# S-COMERCIALES.net
KiCad netlist of a schematic drawn in Altium Designer
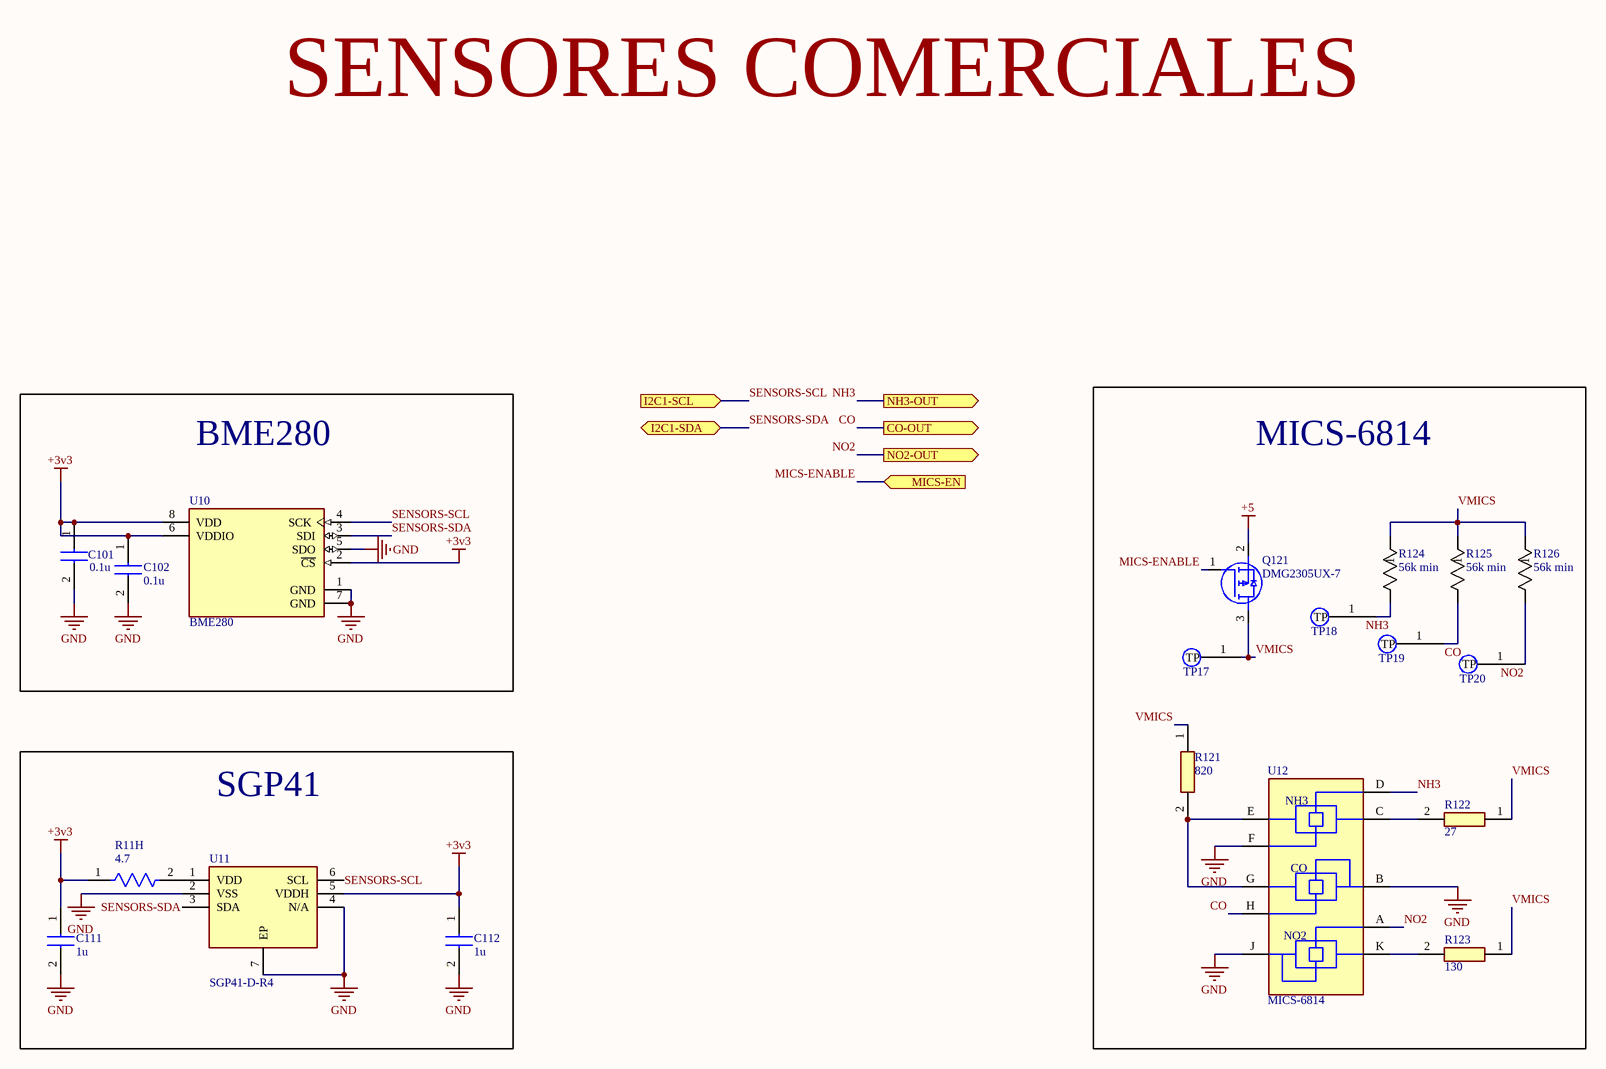
[diagram p0: S-COMERCIALES.SchDoc]

(export (version "E")
  (design (tool "Eeschema 10.0.6"))
  (components
    (comp (ref "C101")
      (value "0.1u")
      (footprint "SamacSys:CAPC1005X22N")
      (description "Capacitor")
      (fields
        (field (name "MANUFACTURER_PART_NUMBER") "GRM152R61A104KE19D")
        (field (name "MOUSER PART NUMBER") "81-GRM152R61A104KE9D")
      )
      (libsource (lib "*") (part "GRM152R61A104KE19D"))
    )
    (comp (ref "C102")
      (value "0.1u")
      (footprint "SamacSys:CAPC1005X22N")
      (description "Capacitor")
      (fields
        (field (name "MANUFACTURER_PART_NUMBER") "GRM152R61A104KE19D")
        (field (name "MOUSER PART NUMBER") "81-GRM152R61A104KE9D")
      )
      (libsource (lib "*") (part "GRM152R61A104KE19D"))
    )
    (comp (ref "C111")
      (value "1u")
      (footprint "SamacSys:GRM15x")
      (description "Capacitor")
      (fields (field (name "MANUFACTURER_PART_NUMBER") "GRM155C71C105ME11J"))
      (libsource (lib "*") (part "GRM155C71C105ME11J"))
    )
    (comp (ref "C112")
      (value "1u")
      (footprint "SamacSys:GRM15x")
      (description "Capacitor")
      (fields (field (name "MANUFACTURER_PART_NUMBER") "GRM155C71C105ME11J"))
      (libsource (lib "*") (part "GRM155C71C105ME11J"))
    )
    (comp (ref "Q121")
      (value "DMG2305UX-7")
      (footprint "SamacSys:SOT96P240X115-3N")
      (description "MOSFET (P-Channel)")
      (fields (field (name "MOUSER PART NUMBER") "621-DMG2305UX-7"))
      (libsource (lib "*") (part "DMG2305UX-7"))
    )
    (comp (ref "R11H")
      (value "4.7")
      (footprint "FP-AF0402-MFG")
      (description "Anti-Sulfurated Chip Resistors Automotive Grade 4.7Ω 1% 200ppm/°C 0402")
      (fields (field (name "TOLERANCE") "1%"))
      (libsource (lib "Altium Content Vault") (part "1029c3af85768c4190bb7ad29bc67b5"))
    )
    (comp (ref "R121")
      (value "820")
      (footprint "SamacSys:RESC2012X70N")
      (description "Resistor")
      (fields
        (field (name "MANUFACTURER_PART_NUMBER") "ERJ-T06J821V")
        (field (name "MOUSER PART NUMBER") "667-ERJ-T06J821V")
      )
      (libsource (lib "*") (part "ERJ-T06J821V"))
    )
    (comp (ref "R122")
      (value "27")
      (footprint "SamacSys:ERJUP6")
      (description "Resistor")
      (fields (field (name "MANUFACTURER_PART_NUMBER") "ERJ-UP6D27R0V"))
      (libsource (lib "*") (part "ERJ-UP6D27R0V"))
    )
    (comp (ref "R123")
      (value "130")
      (footprint "SamacSys:ERJUP6")
      (description "Resistor")
      (fields (field (name "MANUFACTURER_PART_NUMBER") "ERJ-UP6D1300V"))
      (libsource (lib "*") (part "ERJ-UP6D1300V"))
    )
    (comp (ref "R124")
      (value "56k min")
      (footprint "RES_CFR25_6P3X2P4_YAG")
      (description "No Description Available")
      (fields
        (field (name "MANUFACTURER_PART_NUMBER") "CFR-25JR-52-56K")
        (field (name "COPYRIGHT") "Copyright (C) 2025 Ultra Librarian. All rights reserved.")
      )
      (libsource (lib "CFR-25JR-52-56K") (part "CFR-25JR-52-56K"))
    )
    (comp (ref "R125")
      (value "56k min")
      (footprint "RES_CFR25_6P3X2P4_YAG")
      (description "No Description Available")
      (fields
        (field (name "MANUFACTURER_PART_NUMBER") "CFR-25JR-52-56K")
        (field (name "COPYRIGHT") "Copyright (C) 2025 Ultra Librarian. All rights reserved.")
      )
      (libsource (lib "CFR-25JR-52-56K") (part "CFR-25JR-52-56K"))
    )
    (comp (ref "R126")
      (value "56k min")
      (footprint "RES_CFR25_6P3X2P4_YAG")
      (description "No Description Available")
      (fields
        (field (name "MANUFACTURER_PART_NUMBER") "CFR-25JR-52-56K")
        (field (name "COPYRIGHT") "Copyright (C) 2025 Ultra Librarian. All rights reserved.")
      )
      (libsource (lib "CFR-25JR-52-56K") (part "CFR-25JR-52-56K"))
    )
    (comp (ref "TP17")
      (value "Testpoint")
      (footprint "Testpoint_TH")
      (libsource (lib "headers") (part "Testpoint"))
    )
    (comp (ref "TP18")
      (value "Testpoint")
      (footprint "Testpoint_TH")
      (libsource (lib "headers") (part "Testpoint"))
    )
    (comp (ref "TP19")
      (value "Testpoint")
      (footprint "Testpoint_TH")
      (libsource (lib "headers") (part "Testpoint"))
    )
    (comp (ref "TP20")
      (value "Testpoint")
      (footprint "Testpoint_TH")
      (libsource (lib "headers") (part "Testpoint"))
    )
    (comp (ref "U10")
      (value "BME280")
      (footprint "FP-BME280-MFG")
      (description "SENSOR PRESSURE HUMIDITY TEMP")
      (libsource (lib "Altium Content Vault") (part "d58e2f6669bc67e6a2bc6a28610ca79"))
    )
    (comp (ref "U11")
      (value "SGP41-D-R4")
      (footprint "SamacSys:SON80P244X244X95-7N")
      (description "Integrated Circuit")
      (fields (field (name "MOUSER PART NUMBER") "403-SGP41-D-R4"))
      (libsource (lib "*") (part "SGP41-D-R4"))
    )
    (comp (ref "U12")
      (value "MICS-6814")
      (footprint "FP-MICS-6814-MFG")
      (description "SMD CARBON MONOXIDE/NITROGEN DIO")
      (libsource (lib "Altium Content Vault") (part "21e44823f469d6004a0d015ae8a6304"))
    )
  )
  (nets
    (net (code "1") (name "+3v3") (class "Default")
      (node (ref "C101") (pin "1") (pinfunction "1_1") (pintype "passive"))
      (node (ref "C102") (pin "1") (pinfunction "1_1") (pintype "passive"))
      (node (ref "C111") (pin "1") (pinfunction "1_1") (pintype "passive"))
      (node (ref "C112") (pin "1") (pinfunction "1_1") (pintype "passive"))
      (node (ref "R11H") (pin "1") (pinfunction "1_1") (pintype "passive"))
      (node (ref "U10") (pin "2") (pinfunction "~{CS}_2") (pintype "input"))
      (node (ref "U10") (pin "6") (pinfunction "VDDIO_6") (pintype "power_in"))
      (node (ref "U10") (pin "8") (pinfunction "VDD_8") (pintype "power_in"))
      (node (ref "U11") (pin "5") (pinfunction "VDDH_5") (pintype "passive"))
    )
    (net (code "2") (name "+5") (class "Default")
      (node (ref "Q121") (pin "2") (pinfunction "S_2") (pintype "passive"))
    )
    (net (code "3") (name "/CO") (class "Default")
      (node (ref "R125") (pin "2") (pinfunction "2_2") (pintype "passive"))
      (node (ref "TP19") (pin "1") (pinfunction "TP_1") (pintype "passive"))
      (node (ref "U12") (pin "H") (pinfunction "Rs2_RED_H") (pintype "passive"))
    )
    (net (code "4") (name "/MICS-ENABLE") (class "Default")
      (node (ref "Q121") (pin "1") (pinfunction "G_1") (pintype "passive"))
    )
    (net (code "5") (name "/NH3") (class "Default")
      (node (ref "R124") (pin "2") (pinfunction "2_2") (pintype "passive"))
      (node (ref "TP18") (pin "1") (pinfunction "TP_1") (pintype "passive"))
      (node (ref "U12") (pin "D") (pinfunction "Rs1_NH3_D") (pintype "passive"))
    )
    (net (code "6") (name "/NO2") (class "Default")
      (node (ref "R126") (pin "2") (pinfunction "2_2") (pintype "passive"))
      (node (ref "TP20") (pin "1") (pinfunction "TP_1") (pintype "passive"))
      (node (ref "U12") (pin "A") (pinfunction "Rs2_A") (pintype "passive"))
    )
    (net (code "7") (name "/SENSORS-SCL") (class "Default")
      (node (ref "U10") (pin "4") (pinfunction "SCK_4") (pintype "input"))
      (node (ref "U11") (pin "6") (pinfunction "SCL_6") (pintype "passive"))
    )
    (net (code "8") (name "/SENSORS-SDA") (class "Default")
      (node (ref "U10") (pin "3") (pinfunction "SDI_3") (pintype "bidirectional"))
      (node (ref "U11") (pin "3") (pinfunction "SDA_3") (pintype "passive"))
    )
    (net (code "9") (name "/VMICS") (class "Default")
      (node (ref "Q121") (pin "3") (pinfunction "D_3") (pintype "passive"))
      (node (ref "R121") (pin "1") (pinfunction "1_1") (pintype "passive"))
      (node (ref "R122") (pin "1") (pinfunction "1_1") (pintype "passive"))
      (node (ref "R123") (pin "1") (pinfunction "1_1") (pintype "passive"))
      (node (ref "R124") (pin "1") (pinfunction "1_1") (pintype "passive"))
      (node (ref "R125") (pin "1") (pinfunction "1_1") (pintype "passive"))
      (node (ref "R126") (pin "1") (pinfunction "1_1") (pintype "passive"))
      (node (ref "TP17") (pin "1") (pinfunction "TP_1") (pintype "passive"))
    )
    (net (code "10") (name "GND") (class "Default")
      (node (ref "C101") (pin "2") (pinfunction "2_2") (pintype "passive"))
      (node (ref "C102") (pin "2") (pinfunction "2_2") (pintype "passive"))
      (node (ref "C111") (pin "2") (pinfunction "2_2") (pintype "passive"))
      (node (ref "C112") (pin "2") (pinfunction "2_2") (pintype "passive"))
      (node (ref "U10") (pin "1") (pinfunction "GND_1") (pintype "power_in"))
      (node (ref "U10") (pin "5") (pinfunction "SDO_5") (pintype "bidirectional"))
      (node (ref "U10") (pin "7") (pinfunction "GND_7") (pintype "power_in"))
      (node (ref "U11") (pin "2") (pinfunction "VSS_2") (pintype "passive"))
      (node (ref "U11") (pin "4") (pinfunction "N/A_4") (pintype "passive"))
      (node (ref "U11") (pin "7") (pinfunction "EP_7") (pintype "passive"))
      (node (ref "U12") (pin "B") (pinfunction "Rh1_RED/Rs1_RED_B") (pintype "passive"))
      (node (ref "U12") (pin "F") (pinfunction "Rs2_NH3_F") (pintype "passive"))
      (node (ref "U12") (pin "J") (pinfunction "Rh1_OX/Rs1_OX_J") (pintype "passive"))
    )
    (net (code "11") (name "Net-(U11-VDD)") (class "Default")
      (node (ref "R11H") (pin "2") (pinfunction "2_2") (pintype "passive"))
      (node (ref "U11") (pin "1") (pinfunction "VDD_1") (pintype "passive"))
    )
    (net (code "12") (name "Net-(U12-Rh1_NH3)") (class "Default")
      (node (ref "R122") (pin "2") (pinfunction "2_2") (pintype "passive"))
      (node (ref "U12") (pin "C") (pinfunction "Rh1_NH3_C") (pintype "passive"))
    )
    (net (code "13") (name "Net-(U12-Rh2_NH3)") (class "Default")
      (node (ref "R121") (pin "2") (pinfunction "2_2") (pintype "passive"))
      (node (ref "U12") (pin "E") (pinfunction "Rh2_NH3_E") (pintype "passive"))
      (node (ref "U12") (pin "G") (pinfunction "Rh2_RED_G") (pintype "passive"))
    )
    (net (code "14") (name "Net-(U12-Rh2_OX)") (class "Default")
      (node (ref "R123") (pin "2") (pinfunction "2_2") (pintype "passive"))
      (node (ref "U12") (pin "K") (pinfunction "Rh2_OX_K") (pintype "passive"))
    )
  )
)
